# PMI_carte_principale.net
KiCad netlist of a schematic drawn in Altium Designer
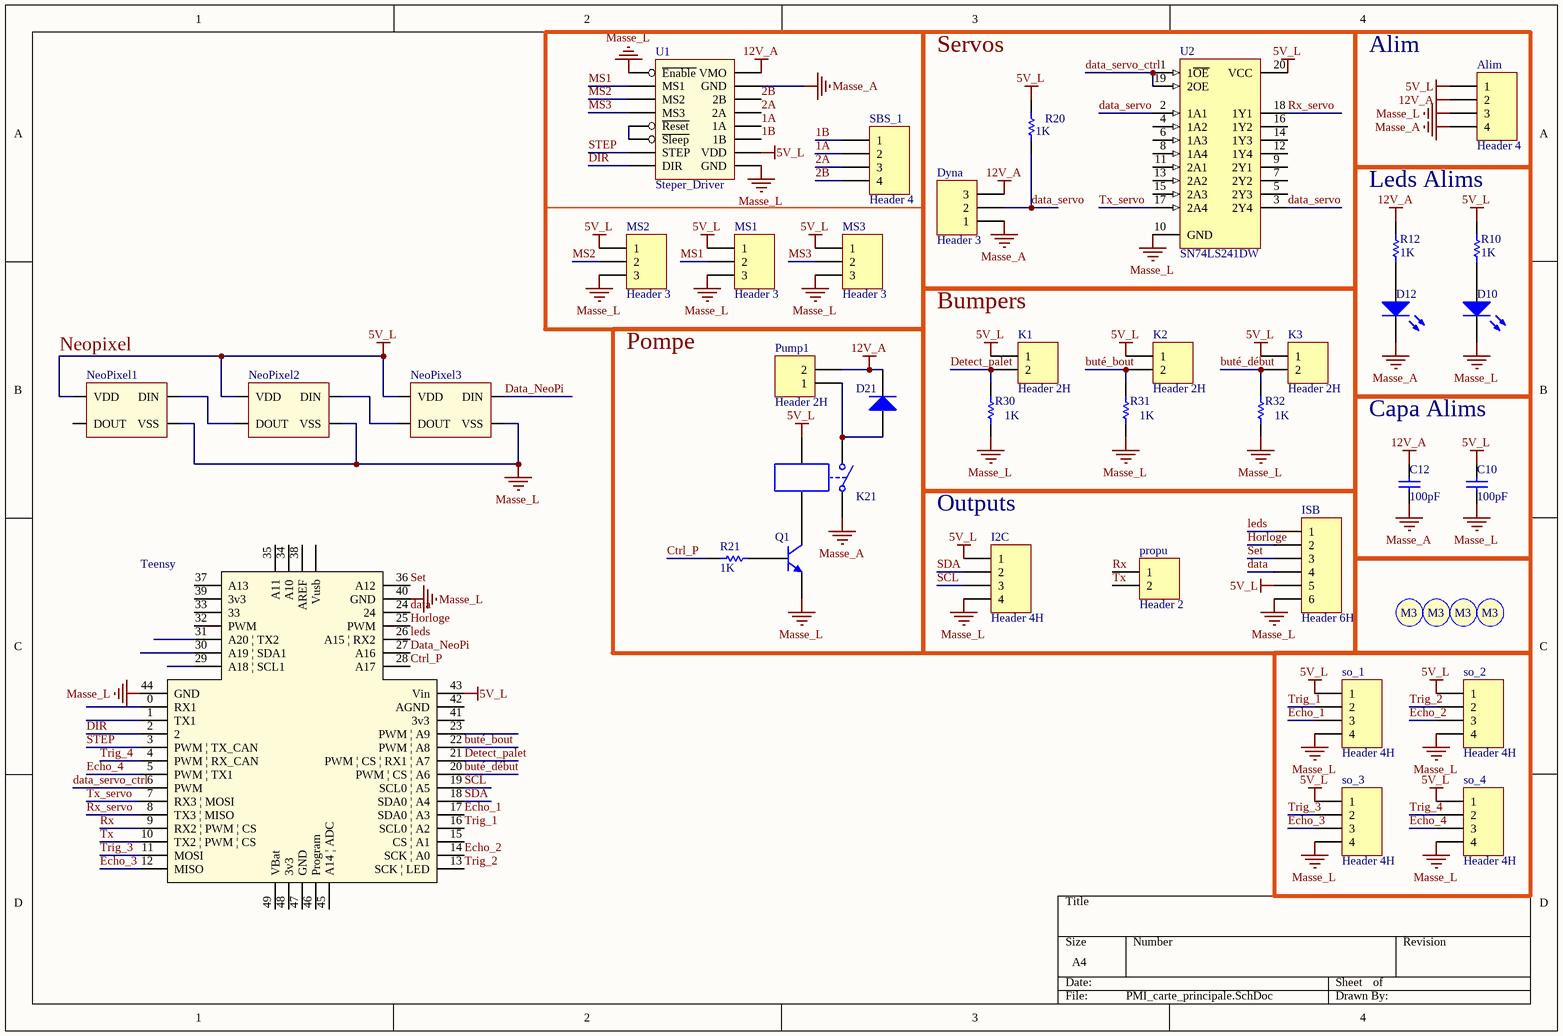
[diagram p0: PMI_carte_principale.SchDoc]

(export (version "E")
  (design (tool "Eeschema 10.0.6"))
  (components
    (comp (ref "Alim")
      (value "Header 4")
      (footprint "Molex_MiniFitJr_2x2")
      (description "Header, 4-Pin")
      (fields (field (name "PUBLISHER") "Altium Limited"))
      (libsource (lib "Miscellaneous Connectors") (part "Header 4"))
    )
    (comp (ref "C10")
      (value "100pF")
      (footprint "Condensateur")
      (description "Capacitor")
      (fields (field (name "Comment") "Cap") (field (name "PUBLISHER") "Altium Limited"))
      (libsource (lib "Miscellaneous Devices") (part "Cap"))
    )
    (comp (ref "C12")
      (value "100pF")
      (footprint "Condensateur")
      (description "Capacitor")
      (fields (field (name "Comment") "Cap") (field (name "PUBLISHER") "Altium Limited"))
      (libsource (lib "Miscellaneous Devices") (part "Cap"))
    )
    (comp (ref "D10")
      (value "LED0")
      (footprint "3.2X1.6X1.1")
      (description "Typical INFRARED GaAs LED")
      (fields (field (name "PUBLISHER") "Altium Limited"))
      (libsource (lib "Miscellaneous Devices") (part "LED0"))
    )
    (comp (ref "D12")
      (value "LED0")
      (footprint "3.2X1.6X1.1")
      (description "Typical INFRARED GaAs LED")
      (fields (field (name "PUBLISHER") "Altium Limited"))
      (libsource (lib "Miscellaneous Devices") (part "LED0"))
    )
    (comp (ref "D21")
      (value "Diode")
      (footprint "3.2X1.6X1.1")
      (description "Default Diode")
      (fields (field (name "PUBLISHER") "Altium Limited"))
      (libsource (lib "Miscellaneous Devices") (part "Diode"))
    )
    (comp (ref "Dyna")
      (value "Header 3")
      (footprint "MOLEX SPOX 3x1 M")
      (description "Header, 3-Pin")
      (fields (field (name "PUBLISHER") "Altium Limited"))
      (libsource (lib "") (part "Header 3_1"))
    )
    (comp (ref "I2C")
      (value "Header 4H")
      (footprint "MOLEX SPOX 4x1 M")
      (description "Header, 4-Pin, Right Angle")
      (fields (field (name "PUBLISHER") "Altium Limited"))
      (libsource (lib "Miscellaneous Connectors") (part "Header 4H"))
    )
    (comp (ref "ISB")
      (value "Header 6H")
      (footprint "MOLEX SPOX 6x1 M")
      (description "Header, 6-Pin, Right Angle")
      (fields (field (name "PUBLISHER") "Altium Limited"))
      (libsource (lib "Miscellaneous Connectors") (part "Header 6H"))
    )
    (comp (ref "K1")
      (value "Header 2H")
      (footprint "MOLEX SPOX 2x1 M")
      (description "Header, 2-Pin, Right Angle")
      (fields (field (name "PUBLISHER") "Altium Limited"))
      (libsource (lib "Miscellaneous Connectors") (part "Header 2H"))
    )
    (comp (ref "K2")
      (value "Header 2H")
      (footprint "MOLEX SPOX 2x1 M")
      (description "Header, 2-Pin, Right Angle")
      (fields (field (name "PUBLISHER") "Altium Limited"))
      (libsource (lib "Miscellaneous Connectors") (part "Header 2H"))
    )
    (comp (ref "K3")
      (value "Header 2H")
      (footprint "MOLEX SPOX 2x1 M")
      (description "Header, 2-Pin, Right Angle")
      (fields (field (name "PUBLISHER") "Altium Limited"))
      (libsource (lib "Miscellaneous Connectors") (part "Header 2H"))
    )
    (comp (ref "K21")
      (value "Relay-SPST")
      (footprint "Relay")
      (description "Single-Pole Single-Throw Relay")
      (fields (field (name "PUBLISHER") "Altium Limited"))
      (libsource (lib "Miscellaneous Devices") (part "Relay-SPST"))
    )
    (comp (ref "MS1")
      (value "Header 3")
      (footprint "HDR1X3")
      (description "Header, 3-Pin")
      (fields (field (name "PUBLISHER") "Altium Limited"))
      (libsource (lib "Miscellaneous Connectors") (part "Header 3"))
    )
    (comp (ref "MS2")
      (value "Header 3")
      (footprint "HDR1X3")
      (description "Header, 3-Pin")
      (fields (field (name "PUBLISHER") "Altium Limited"))
      (libsource (lib "Miscellaneous Connectors") (part "Header 3"))
    )
    (comp (ref "MS3")
      (value "Header 3")
      (footprint "HDR1X3")
      (description "Header, 3-Pin")
      (fields (field (name "PUBLISHER") "Altium Limited"))
      (libsource (lib "Miscellaneous Connectors") (part "Header 3"))
    )
    (comp (ref "NeoPixel1")
      (value "NeoPixel1")
      (footprint "Robot_2019:Neopixel")
      (libsource (lib "Robot_2019") (part "NeoPixel"))
    )
    (comp (ref "NeoPixel2")
      (value "NeoPixel2")
      (footprint "Robot_2019:Neopixel")
      (libsource (lib "Robot_2019") (part "NeoPixel"))
    )
    (comp (ref "NeoPixel3")
      (value "NeoPixel3")
      (footprint "Neopixel")
      (libsource (lib "Robot_2019") (part "NeoPixel"))
    )
    (comp (ref "propu")
      (value "Header 2")
      (footprint "MOLEX SPOX 2x1 M")
      (description "Header, 2-Pin")
      (fields (field (name "PUBLISHER") "Altium Limited"))
      (libsource (lib "Miscellaneous Connectors") (part "Header 2"))
    )
    (comp (ref "Pump1")
      (value "Header 2H")
      (footprint "MOLEX SPOX 2x1 M")
      (description "Header, 2-Pin, Right Angle")
      (fields (field (name "PUBLISHER") "Altium Limited"))
      (libsource (lib "") (part "Header 2H_1"))
    )
    (comp (ref "Q1")
      (value "NPN")
      (footprint "TO-226-AA")
      (description "NPN Bipolar Transistor")
      (fields (field (name "PUBLISHER") "Altium Limited"))
      (libsource (lib "Miscellaneous Devices") (part "NPN"))
    )
    (comp (ref "R10")
      (value "1K")
      (footprint "3.2X1.6X1.1")
      (description "Resistor")
      (fields (field (name "Comment") "Res_5V_A") (field (name "PUBLISHER") "Altium Limited"))
      (libsource (lib "Miscellaneous Devices") (part "Res1"))
    )
    (comp (ref "R12")
      (value "1K")
      (footprint "3.2X1.6X1.1")
      (description "Resistor")
      (fields (field (name "Comment") "Res_5V_A") (field (name "PUBLISHER") "Altium Limited"))
      (libsource (lib "Miscellaneous Devices") (part "Res1"))
    )
    (comp (ref "R20")
      (value "1K")
      (footprint "3.2X1.6X1.1")
      (description "Resistor")
      (fields (field (name "Comment") "Res_5V_A") (field (name "PUBLISHER") "Altium Limited"))
      (libsource (lib "Miscellaneous Devices") (part "Res1"))
    )
    (comp (ref "R21")
      (value "1K")
      (footprint "3.2X1.6X1.1")
      (description "Resistor")
      (fields (field (name "Comment") "ResP") (field (name "PUBLISHER") "Altium Limited"))
      (libsource (lib "Miscellaneous Devices") (part "Res1"))
    )
    (comp (ref "R30")
      (value "1K")
      (footprint "3.2X1.6X1.1")
      (description "Resistor")
      (fields (field (name "Comment") "Res1") (field (name "PUBLISHER") "Altium Limited"))
      (libsource (lib "Miscellaneous Devices") (part "Res1"))
    )
    (comp (ref "R31")
      (value "1K")
      (footprint "3.2X1.6X1.1")
      (description "Resistor")
      (fields (field (name "Comment") "Res1") (field (name "PUBLISHER") "Altium Limited"))
      (libsource (lib "Miscellaneous Devices") (part "Res1"))
    )
    (comp (ref "R32")
      (value "1K")
      (footprint "3.2X1.6X1.1")
      (description "Resistor")
      (fields (field (name "Comment") "Res1") (field (name "PUBLISHER") "Altium Limited"))
      (libsource (lib "Miscellaneous Devices") (part "Res1"))
    )
    (comp (ref "SBS_1")
      (value "Header 4")
      (footprint "MOLEX SPOX 4x1 M")
      (description "Header, 4-Pin")
      (fields (field (name "PUBLISHER") "Altium Limited"))
      (libsource (lib "Miscellaneous Connectors") (part "Header 4"))
    )
    (comp (ref "Screw_1")
      (value "Screw M3")
      (footprint "Robot_2019:Screw M3")
      (libsource (lib "Robot_2019") (part "Screw M3"))
    )
    (comp (ref "Screw_2")
      (value "Screw M3")
      (footprint "Robot_2019:Screw M3")
      (libsource (lib "Robot_2019") (part "Screw M3"))
    )
    (comp (ref "Screw_3")
      (value "Screw M3")
      (footprint "Robot_2019:Screw M3")
      (libsource (lib "Robot_2019") (part "Screw M3"))
    )
    (comp (ref "Screw_4")
      (value "Screw M3")
      (footprint "Robot_2019:Screw M3")
      (libsource (lib "Robot_2019") (part "Screw M3"))
    )
    (comp (ref "so_1")
      (value "Header 4H")
      (footprint "MOLEX SPOX 4x1 M")
      (description "Header, 4-Pin, Right Angle")
      (fields (field (name "PUBLISHER") "Altium Limited"))
      (libsource (lib "Miscellaneous Connectors") (part "Header 4H"))
    )
    (comp (ref "so_2")
      (value "Header 4H")
      (footprint "MOLEX SPOX 4x1 M")
      (description "Header, 4-Pin, Right Angle")
      (fields (field (name "PUBLISHER") "Altium Limited"))
      (libsource (lib "Miscellaneous Connectors") (part "Header 4H"))
    )
    (comp (ref "so_3")
      (value "Header 4H")
      (footprint "MOLEX SPOX 4x1 M")
      (description "Header, 4-Pin, Right Angle")
      (fields (field (name "PUBLISHER") "Altium Limited"))
      (libsource (lib "Miscellaneous Connectors") (part "Header 4H"))
    )
    (comp (ref "so_4")
      (value "Header 4H")
      (footprint "MOLEX SPOX 4x1 M")
      (description "Header, 4-Pin, Right Angle")
      (fields (field (name "PUBLISHER") "Altium Limited"))
      (libsource (lib "Miscellaneous Connectors") (part "Header 4H"))
    )
    (comp (ref "Teensy")
      (value "Teensy 3.2")
      (footprint "Robot_2019:teensy")
      (libsource (lib "Robot_2019") (part "teensy3.2"))
    )
    (comp (ref "U1")
      (value "Steper_Driver")
      (footprint "DRV8825")
      (description "A4988")
      (libsource (lib "Robot_2019") (part "Steper_Driver"))
    )
    (comp (ref "U2")
      (value "SN74LS241DW")
      (footprint "DW020_N")
      (description "Octal Buffer and Line Driver with 3-State Outputs")
      (fields (field (name "PUBLISHER") "Altium Limited"))
      (libsource (lib "TI Logic Buffer Line Driver") (part "SN74LS241DW"))
    )
  )
  (nets
    (net (code "1") (name "/1A") (class "Default")
      (node (ref "SBS_1") (pin "2") (pinfunction "2_2") (pintype "passive"))
      (node (ref "U1") (pin "12") (pinfunction "1A_12") (pintype "passive"))
    )
    (net (code "2") (name "/1B") (class "Default")
      (node (ref "SBS_1") (pin "1") (pinfunction "1_1") (pintype "passive"))
      (node (ref "U1") (pin "11") (pinfunction "1B_11") (pintype "passive"))
    )
    (net (code "3") (name "/2A") (class "Default")
      (node (ref "SBS_1") (pin "3") (pinfunction "3_3") (pintype "passive"))
      (node (ref "U1") (pin "13") (pinfunction "2A_13") (pintype "passive"))
    )
    (net (code "4") (name "/2B") (class "Default")
      (node (ref "SBS_1") (pin "4") (pinfunction "4_4") (pintype "passive"))
      (node (ref "U1") (pin "14") (pinfunction "2B_14") (pintype "passive"))
    )
    (net (code "8") (name "/Ctrl_P") (class "Default")
      (node (ref "R21") (pin "1") (pinfunction "1_1") (pintype "passive"))
      (node (ref "Teensy") (pin "28") (pinfunction "A17_28") (pintype "passive"))
    )
    (net (code "9") (name "/DIR") (class "Default")
      (node (ref "Teensy") (pin "2") (pinfunction "2_2") (pintype "passive"))
      (node (ref "U1") (pin "8") (pinfunction "DIR_8") (pintype "passive"))
    )
    (net (code "10") (name "/Data_NeoPi") (class "Default")
      (node (ref "NeoPixel3") (pin "3") (pinfunction "DIN_3") (pintype "passive"))
      (node (ref "Teensy") (pin "27") (pinfunction "A16_27") (pintype "passive"))
    )
    (net (code "11") (name "/Detect_palet") (class "Default")
      (node (ref "K1") (pin "2") (pinfunction "2_2") (pintype "passive"))
      (node (ref "R30") (pin "2") (pinfunction "2_2") (pintype "passive"))
      (node (ref "Teensy") (pin "21") (pinfunction "PWM_¦_CS_¦_RX1_¦_A7_21") (pintype "passive"))
    )
    (net (code "12") (name "/Echo_1") (class "Default")
      (node (ref "Teensy") (pin "17") (pinfunction "SDA0_¦_A3_17") (pintype "passive"))
      (node (ref "so_1") (pin "3") (pinfunction "3_3") (pintype "passive"))
    )
    (net (code "13") (name "/Echo_2") (class "Default")
      (node (ref "Teensy") (pin "14") (pinfunction "SCK_¦_A0_14") (pintype "passive"))
      (node (ref "so_2") (pin "3") (pinfunction "3_3") (pintype "passive"))
    )
    (net (code "14") (name "/Echo_3") (class "Default")
      (node (ref "Teensy") (pin "12") (pinfunction "MISO_12") (pintype "passive"))
      (node (ref "so_3") (pin "3") (pinfunction "3_3") (pintype "passive"))
    )
    (net (code "15") (name "/Echo_4") (class "Default")
      (node (ref "Teensy") (pin "5") (pinfunction "PWM_¦_TX1_5") (pintype "passive"))
      (node (ref "so_4") (pin "3") (pinfunction "3_3") (pintype "passive"))
    )
    (net (code "16") (name "/Horloge") (class "Default")
      (node (ref "ISB") (pin "2") (pinfunction "2_2") (pintype "passive"))
      (node (ref "Teensy") (pin "25") (pinfunction "PWM_25") (pintype "passive"))
    )
    (net (code "18") (name "/MS1") (class "Default")
      (node (ref "MS1") (pin "2") (pinfunction "2_2") (pintype "passive"))
      (node (ref "U1") (pin "2") (pinfunction "MS1_2") (pintype "passive"))
    )
    (net (code "19") (name "/MS2") (class "Default")
      (node (ref "MS2") (pin "2") (pinfunction "2_2") (pintype "passive"))
      (node (ref "U1") (pin "3") (pinfunction "MS2_3") (pintype "passive"))
    )
    (net (code "20") (name "/MS3") (class "Default")
      (node (ref "MS3") (pin "2") (pinfunction "2_2") (pintype "passive"))
      (node (ref "U1") (pin "4") (pinfunction "MS3_4") (pintype "passive"))
    )
    (net (code "23") (name "/Rx") (class "Default")
      (node (ref "Teensy") (pin "9") (pinfunction "RX2_¦_PWM_¦_CS_9") (pintype "passive"))
      (node (ref "propu") (pin "1") (pinfunction "1_1") (pintype "passive"))
    )
    (net (code "24") (name "/Rx_servo") (class "Default")
      (node (ref "Teensy") (pin "8") (pinfunction "TX3_¦_MISO_8") (pintype "passive"))
      (node (ref "U2") (pin "18") (pinfunction "1Y1_18") (pintype "tri_state"))
    )
    (net (code "25") (name "/SCL") (class "Default")
      (node (ref "I2C") (pin "3") (pinfunction "3_3") (pintype "passive"))
      (node (ref "Teensy") (pin "19") (pinfunction "SCL0_¦_A5_19") (pintype "passive"))
    )
    (net (code "26") (name "/SDA") (class "Default")
      (node (ref "I2C") (pin "2") (pinfunction "2_2") (pintype "passive"))
      (node (ref "Teensy") (pin "18") (pinfunction "SDA0_¦_A4_18") (pintype "passive"))
    )
    (net (code "27") (name "/STEP") (class "Default")
      (node (ref "Teensy") (pin "3") (pinfunction "PWM_¦_TX_CAN_3") (pintype "passive"))
      (node (ref "U1") (pin "7") (pinfunction "STEP_7") (pintype "passive"))
    )
    (net (code "29") (name "/Set") (class "Default")
      (node (ref "ISB") (pin "3") (pinfunction "3_3") (pintype "passive"))
      (node (ref "Teensy") (pin "36") (pinfunction "A12_36") (pintype "passive"))
    )
    (net (code "30") (name "/Trig_1") (class "Default")
      (node (ref "Teensy") (pin "16") (pinfunction "SCL0_¦_A2_16") (pintype "passive"))
      (node (ref "so_1") (pin "2") (pinfunction "2_2") (pintype "passive"))
    )
    (net (code "31") (name "/Trig_2") (class "Default")
      (node (ref "Teensy") (pin "13") (pinfunction "SCK_¦_LED_13") (pintype "passive"))
      (node (ref "so_2") (pin "2") (pinfunction "2_2") (pintype "passive"))
    )
    (net (code "32") (name "/Trig_3") (class "Default")
      (node (ref "Teensy") (pin "11") (pinfunction "MOSI_11") (pintype "passive"))
      (node (ref "so_3") (pin "2") (pinfunction "2_2") (pintype "passive"))
    )
    (net (code "33") (name "/Trig_4") (class "Default")
      (node (ref "Teensy") (pin "4") (pinfunction "PWM_¦_RX_CAN_4") (pintype "passive"))
      (node (ref "so_4") (pin "2") (pinfunction "2_2") (pintype "passive"))
    )
    (net (code "34") (name "/Tx") (class "Default")
      (node (ref "Teensy") (pin "10") (pinfunction "TX2_¦_PWM_¦_CS_10") (pintype "passive"))
      (node (ref "propu") (pin "2") (pinfunction "2_2") (pintype "passive"))
    )
    (net (code "35") (name "/Tx_servo") (class "Default")
      (node (ref "Teensy") (pin "7") (pinfunction "RX3_¦_MOSI_7") (pintype "passive"))
      (node (ref "U2") (pin "17") (pinfunction "2A4_17") (pintype "input"))
    )
    (net (code "36") (name "/buté_bout") (class "Default")
      (node (ref "K2") (pin "2") (pinfunction "2_2") (pintype "passive"))
      (node (ref "R31") (pin "2") (pinfunction "2_2") (pintype "passive"))
      (node (ref "Teensy") (pin "22") (pinfunction "PWM_¦_A8_22") (pintype "passive"))
    )
    (net (code "37") (name "/buté_début") (class "Default")
      (node (ref "K3") (pin "2") (pinfunction "2_2") (pintype "passive"))
      (node (ref "R32") (pin "2") (pinfunction "2_2") (pintype "passive"))
      (node (ref "Teensy") (pin "20") (pinfunction "PWM_¦_CS_¦_A6_20") (pintype "passive"))
    )
    (net (code "38") (name "/data") (class "Default")
      (node (ref "ISB") (pin "4") (pinfunction "4_4") (pintype "passive"))
      (node (ref "Teensy") (pin "24") (pinfunction "24_24") (pintype "passive"))
    )
    (net (code "39") (name "/data_servo") (class "Default")
      (node (ref "Dyna") (pin "2") (pinfunction "2_2") (pintype "passive"))
      (node (ref "R20") (pin "2") (pinfunction "2_2") (pintype "passive"))
      (node (ref "U2") (pin "2") (pinfunction "1A1_2") (pintype "input"))
      (node (ref "U2") (pin "3") (pinfunction "2Y4_3") (pintype "tri_state"))
    )
    (net (code "40") (name "/data_servo_ctrl") (class "Default")
      (node (ref "Teensy") (pin "6") (pinfunction "PWM_6") (pintype "passive"))
      (node (ref "U2") (pin "1") (pinfunction "1~{OE}_1") (pintype "input"))
      (node (ref "U2") (pin "19") (pinfunction "2OE_19") (pintype "input"))
    )
    (net (code "41") (name "/leds") (class "Default")
      (node (ref "ISB") (pin "1") (pinfunction "1_1") (pintype "passive"))
      (node (ref "Teensy") (pin "26") (pinfunction "A15_¦_RX2_26") (pintype "passive"))
    )
    (net (code "42") (name "5V_L") (class "Default")
      (node (ref "Alim") (pin "1") (pinfunction "1_1") (pintype "passive"))
      (node (ref "C10") (pin "1") (pinfunction "1_1") (pintype "passive"))
      (node (ref "I2C") (pin "1") (pinfunction "1_1") (pintype "passive"))
      (node (ref "ISB") (pin "5") (pinfunction "5_5") (pintype "passive"))
      (node (ref "K1") (pin "1") (pinfunction "1_1") (pintype "passive"))
      (node (ref "K2") (pin "1") (pinfunction "1_1") (pintype "passive"))
      (node (ref "K21") (pin "4") (pinfunction "4_4") (pintype "passive"))
      (node (ref "K3") (pin "1") (pinfunction "1_1") (pintype "passive"))
      (node (ref "MS1") (pin "1") (pinfunction "1_1") (pintype "passive"))
      (node (ref "MS2") (pin "1") (pinfunction "1_1") (pintype "passive"))
      (node (ref "MS3") (pin "1") (pinfunction "1_1") (pintype "passive"))
      (node (ref "NeoPixel1") (pin "4") (pinfunction "VDD_4") (pintype "passive"))
      (node (ref "NeoPixel2") (pin "4") (pinfunction "VDD_4") (pintype "passive"))
      (node (ref "NeoPixel3") (pin "4") (pinfunction "VDD_4") (pintype "passive"))
      (node (ref "R10") (pin "2") (pinfunction "2_2") (pintype "passive"))
      (node (ref "R20") (pin "1") (pinfunction "1_1") (pintype "passive"))
      (node (ref "Teensy") (pin "43") (pinfunction "Vin_43") (pintype "passive"))
      (node (ref "U1") (pin "10") (pinfunction "VDD_10") (pintype "passive"))
      (node (ref "U2") (pin "20") (pinfunction "VCC_20") (pintype "power_in"))
      (node (ref "so_1") (pin "1") (pinfunction "1_1") (pintype "passive"))
      (node (ref "so_2") (pin "1") (pinfunction "1_1") (pintype "passive"))
      (node (ref "so_3") (pin "1") (pinfunction "1_1") (pintype "passive"))
      (node (ref "so_4") (pin "1") (pinfunction "1_1") (pintype "passive"))
    )
    (net (code "43") (name "12V_A") (class "Default")
      (node (ref "Alim") (pin "2") (pinfunction "2_2") (pintype "passive"))
      (node (ref "C12") (pin "1") (pinfunction "1_1") (pintype "passive"))
      (node (ref "D21") (pin "2") (pinfunction "K_2") (pintype "passive"))
      (node (ref "Dyna") (pin "3") (pinfunction "3_3") (pintype "passive"))
      (node (ref "Pump1") (pin "2") (pinfunction "2_2") (pintype "passive"))
      (node (ref "R12") (pin "2") (pinfunction "2_2") (pintype "passive"))
      (node (ref "U1") (pin "16") (pinfunction "VMO_16") (pintype "passive"))
    )
    (net (code "44") (name "Masse_A") (class "Default")
      (node (ref "Alim") (pin "4") (pinfunction "4_4") (pintype "passive"))
      (node (ref "C12") (pin "2") (pinfunction "2_2") (pintype "passive"))
      (node (ref "D12") (pin "2") (pinfunction "K_2") (pintype "passive"))
      (node (ref "Dyna") (pin "1") (pinfunction "1_1") (pintype "passive"))
      (node (ref "K21") (pin "1") (pinfunction "1_1") (pintype "passive"))
      (node (ref "U1") (pin "15") (pinfunction "GND_15") (pintype "passive"))
    )
    (net (code "45") (name "Masse_L") (class "Default")
      (node (ref "Alim") (pin "3") (pinfunction "3_3") (pintype "passive"))
      (node (ref "C10") (pin "2") (pinfunction "2_2") (pintype "passive"))
      (node (ref "D10") (pin "2") (pinfunction "K_2") (pintype "passive"))
      (node (ref "I2C") (pin "4") (pinfunction "4_4") (pintype "passive"))
      (node (ref "ISB") (pin "6") (pinfunction "6_6") (pintype "passive"))
      (node (ref "MS1") (pin "3") (pinfunction "3_3") (pintype "passive"))
      (node (ref "MS2") (pin "3") (pinfunction "3_3") (pintype "passive"))
      (node (ref "MS3") (pin "3") (pinfunction "3_3") (pintype "passive"))
      (node (ref "NeoPixel1") (pin "2") (pinfunction "VSS_2") (pintype "passive"))
      (node (ref "NeoPixel2") (pin "2") (pinfunction "VSS_2") (pintype "passive"))
      (node (ref "NeoPixel3") (pin "2") (pinfunction "VSS_2") (pintype "passive"))
      (node (ref "Q1") (pin "3") (pinfunction "E_3") (pintype "passive"))
      (node (ref "R30") (pin "1") (pinfunction "1_1") (pintype "passive"))
      (node (ref "R31") (pin "1") (pinfunction "1_1") (pintype "passive"))
      (node (ref "R32") (pin "1") (pinfunction "1_1") (pintype "passive"))
      (node (ref "Teensy") (pin "40") (pinfunction "GND_40") (pintype "passive"))
      (node (ref "Teensy") (pin "44") (pinfunction "GND_44") (pintype "passive"))
      (node (ref "U1") (pin "1") (pinfunction "~{Enable}_1") (pintype "passive"))
      (node (ref "U1") (pin "9") (pinfunction "GND_9") (pintype "passive"))
      (node (ref "U2") (pin "10") (pinfunction "GND_10") (pintype "power_in"))
      (node (ref "so_1") (pin "4") (pinfunction "4_4") (pintype "passive"))
      (node (ref "so_2") (pin "4") (pinfunction "4_4") (pintype "passive"))
      (node (ref "so_3") (pin "4") (pinfunction "4_4") (pintype "passive"))
      (node (ref "so_4") (pin "4") (pinfunction "4_4") (pintype "passive"))
    )
    (net (code "46") (name "Net-(D10-A)") (class "Default")
      (node (ref "D10") (pin "1") (pinfunction "A_1") (pintype "passive"))
      (node (ref "R10") (pin "1") (pinfunction "1_1") (pintype "passive"))
    )
    (net (code "47") (name "Net-(D12-A)") (class "Default")
      (node (ref "D12") (pin "1") (pinfunction "A_1") (pintype "passive"))
      (node (ref "R12") (pin "1") (pinfunction "1_1") (pintype "passive"))
    )
    (net (code "48") (name "Net-(D21-A)") (class "Default")
      (node (ref "D21") (pin "1") (pinfunction "A_1") (pintype "passive"))
      (node (ref "K21") (pin "2") (pinfunction "2_2") (pintype "passive"))
      (node (ref "Pump1") (pin "1") (pinfunction "1_1") (pintype "passive"))
    )
    (net (code "49") (name "Net-(NeoPixel1-DIN)") (class "Default")
      (node (ref "NeoPixel1") (pin "3") (pinfunction "DIN_3") (pintype "passive"))
      (node (ref "NeoPixel2") (pin "1") (pinfunction "DOUT_1") (pintype "passive"))
    )
    (net (code "50") (name "Net-(NeoPixel2-DIN)") (class "Default")
      (node (ref "NeoPixel2") (pin "3") (pinfunction "DIN_3") (pintype "passive"))
      (node (ref "NeoPixel3") (pin "1") (pinfunction "DOUT_1") (pintype "passive"))
    )
    (net (code "51") (name "Net-(Q1-B)") (class "Default")
      (node (ref "Q1") (pin "2") (pinfunction "B_2") (pintype "passive"))
      (node (ref "R21") (pin "2") (pinfunction "2_2") (pintype "passive"))
    )
    (net (code "52") (name "Net-(Q1-C)") (class "Default")
      (node (ref "K21") (pin "3") (pinfunction "3_3") (pintype "passive"))
      (node (ref "Q1") (pin "1") (pinfunction "C_1") (pintype "passive"))
    )
    (net (code "53") (name "Net-(U1-~{Reset})") (class "Default")
      (node (ref "U1") (pin "5") (pinfunction "~{Reset}_5") (pintype "passive"))
      (node (ref "U1") (pin "6") (pinfunction "~{Sleep}_6") (pintype "passive"))
    )
    (net (code "54") (name "unconnected-(NeoPixel1-DOUT-Pad1)") (class "Default")
      (node (ref "NeoPixel1") (pin "1") (pinfunction "DOUT_1") (pintype "passive"))
    )
    (net (code "55") (name "unconnected-(Teensy-3v3-Pad39)") (class "Default")
      (node (ref "Teensy") (pin "39") (pinfunction "3v3_39") (pintype "passive"))
    )
    (net (code "56") (name "unconnected-(Teensy-3v3-Pad41)") (class "Default")
      (node (ref "Teensy") (pin "41") (pinfunction "3v3_41") (pintype "passive"))
    )
    (net (code "57") (name "unconnected-(Teensy-3v3-Pad48)") (class "Default")
      (node (ref "Teensy") (pin "48") (pinfunction "3v3_48") (pintype "passive"))
    )
    (net (code "58") (name "unconnected-(Teensy-A10-Pad34)") (class "Default")
      (node (ref "Teensy") (pin "34") (pinfunction "A10_34") (pintype "passive"))
    )
    (net (code "59") (name "unconnected-(Teensy-A11-Pad35)") (class "Default")
      (node (ref "Teensy") (pin "35") (pinfunction "A11_35") (pintype "passive"))
    )
    (net (code "60") (name "unconnected-(Teensy-A13-Pad37)") (class "Default")
      (node (ref "Teensy") (pin "37") (pinfunction "A13_37") (pintype "passive"))
    )
    (net (code "61") (name "unconnected-(Teensy-A14_¦_ADC-Pad45)") (class "Default")
      (node (ref "Teensy") (pin "45") (pinfunction "A14_¦_ADC_45") (pintype "passive"))
    )
    (net (code "62") (name "unconnected-(Teensy-A18_¦_SCL1-Pad29)") (class "Default")
      (node (ref "Teensy") (pin "29") (pinfunction "A18_¦_SCL1_29") (pintype "passive"))
    )
    (net (code "63") (name "unconnected-(Teensy-A19_¦_SDA1-Pad30)") (class "Default")
      (node (ref "Teensy") (pin "30") (pinfunction "A19_¦_SDA1_30") (pintype "passive"))
    )
    (net (code "64") (name "unconnected-(Teensy-A20_¦_TX2-Pad31)") (class "Default")
      (node (ref "Teensy") (pin "31") (pinfunction "A20_¦_TX2_31") (pintype "passive"))
    )
    (net (code "65") (name "unconnected-(Teensy-AGND-Pad42)") (class "Default")
      (node (ref "Teensy") (pin "42") (pinfunction "AGND_42") (pintype "passive"))
    )
    (net (code "66") (name "unconnected-(Teensy-AREF-Pad38)") (class "Default")
      (node (ref "Teensy") (pin "38") (pinfunction "AREF_38") (pintype "passive"))
    )
    (net (code "67") (name "unconnected-(Teensy-CS_¦_A1-Pad15)") (class "Default")
      (node (ref "Teensy") (pin "15") (pinfunction "CS_¦_A1_15") (pintype "passive"))
    )
    (net (code "68") (name "unconnected-(Teensy-GND-Pad47)") (class "Default")
      (node (ref "Teensy") (pin "47") (pinfunction "GND_47") (pintype "passive"))
    )
    (net (code "69") (name "unconnected-(Teensy-PWM-Pad32)") (class "Default")
      (node (ref "Teensy") (pin "32") (pinfunction "PWM_32") (pintype "passive"))
    )
    (net (code "70") (name "unconnected-(Teensy-PWM_¦_A9-Pad23)") (class "Default")
      (node (ref "Teensy") (pin "23") (pinfunction "PWM_¦_A9_23") (pintype "passive"))
    )
    (net (code "71") (name "unconnected-(Teensy-Pad33)") (class "Default")
      (node (ref "Teensy") (pin "33") (pinfunction "33_33") (pintype "passive"))
    )
    (net (code "72") (name "unconnected-(Teensy-Program-Pad46)") (class "Default")
      (node (ref "Teensy") (pin "46") (pinfunction "Program_46") (pintype "passive"))
    )
    (net (code "73") (name "unconnected-(Teensy-RX1-Pad0)") (class "Default")
      (node (ref "Teensy") (pin "0") (pinfunction "RX1_0") (pintype "passive"))
    )
    (net (code "74") (name "unconnected-(Teensy-TX1-Pad1)") (class "Default")
      (node (ref "Teensy") (pin "1") (pinfunction "TX1_1") (pintype "passive"))
    )
    (net (code "75") (name "unconnected-(Teensy-VBat-Pad49)") (class "Default")
      (node (ref "Teensy") (pin "49") (pinfunction "VBat_49") (pintype "passive"))
    )
    (net (code "76") (name "unconnected-(Teensy-Vusb-Pad50)") (class "Default")
      (node (ref "Teensy") (pin "50") (pinfunction "Vusb_50") (pintype "passive"))
    )
    (net (code "77") (name "unconnected-(U2-1A2-Pad4)") (class "Default")
      (node (ref "U2") (pin "4") (pinfunction "1A2_4") (pintype "input"))
    )
    (net (code "78") (name "unconnected-(U2-1A3-Pad6)") (class "Default")
      (node (ref "U2") (pin "6") (pinfunction "1A3_6") (pintype "input"))
    )
    (net (code "79") (name "unconnected-(U2-1A4-Pad8)") (class "Default")
      (node (ref "U2") (pin "8") (pinfunction "1A4_8") (pintype "input"))
    )
    (net (code "80") (name "unconnected-(U2-1Y2-Pad16)") (class "Default")
      (node (ref "U2") (pin "16") (pinfunction "1Y2_16") (pintype "tri_state"))
    )
    (net (code "81") (name "unconnected-(U2-1Y3-Pad14)") (class "Default")
      (node (ref "U2") (pin "14") (pinfunction "1Y3_14") (pintype "tri_state"))
    )
    (net (code "82") (name "unconnected-(U2-1Y4-Pad12)") (class "Default")
      (node (ref "U2") (pin "12") (pinfunction "1Y4_12") (pintype "tri_state"))
    )
    (net (code "83") (name "unconnected-(U2-2A1-Pad11)") (class "Default")
      (node (ref "U2") (pin "11") (pinfunction "2A1_11") (pintype "input"))
    )
    (net (code "84") (name "unconnected-(U2-2A2-Pad13)") (class "Default")
      (node (ref "U2") (pin "13") (pinfunction "2A2_13") (pintype "input"))
    )
    (net (code "85") (name "unconnected-(U2-2A3-Pad15)") (class "Default")
      (node (ref "U2") (pin "15") (pinfunction "2A3_15") (pintype "input"))
    )
    (net (code "86") (name "unconnected-(U2-2Y1-Pad9)") (class "Default")
      (node (ref "U2") (pin "9") (pinfunction "2Y1_9") (pintype "tri_state"))
    )
    (net (code "87") (name "unconnected-(U2-2Y2-Pad7)") (class "Default")
      (node (ref "U2") (pin "7") (pinfunction "2Y2_7") (pintype "tri_state"))
    )
    (net (code "88") (name "unconnected-(U2-2Y3-Pad5)") (class "Default")
      (node (ref "U2") (pin "5") (pinfunction "2Y3_5") (pintype "tri_state"))
    )
  )
)
